# USB.net
KiCad netlist of a schematic drawn in Altium Designer
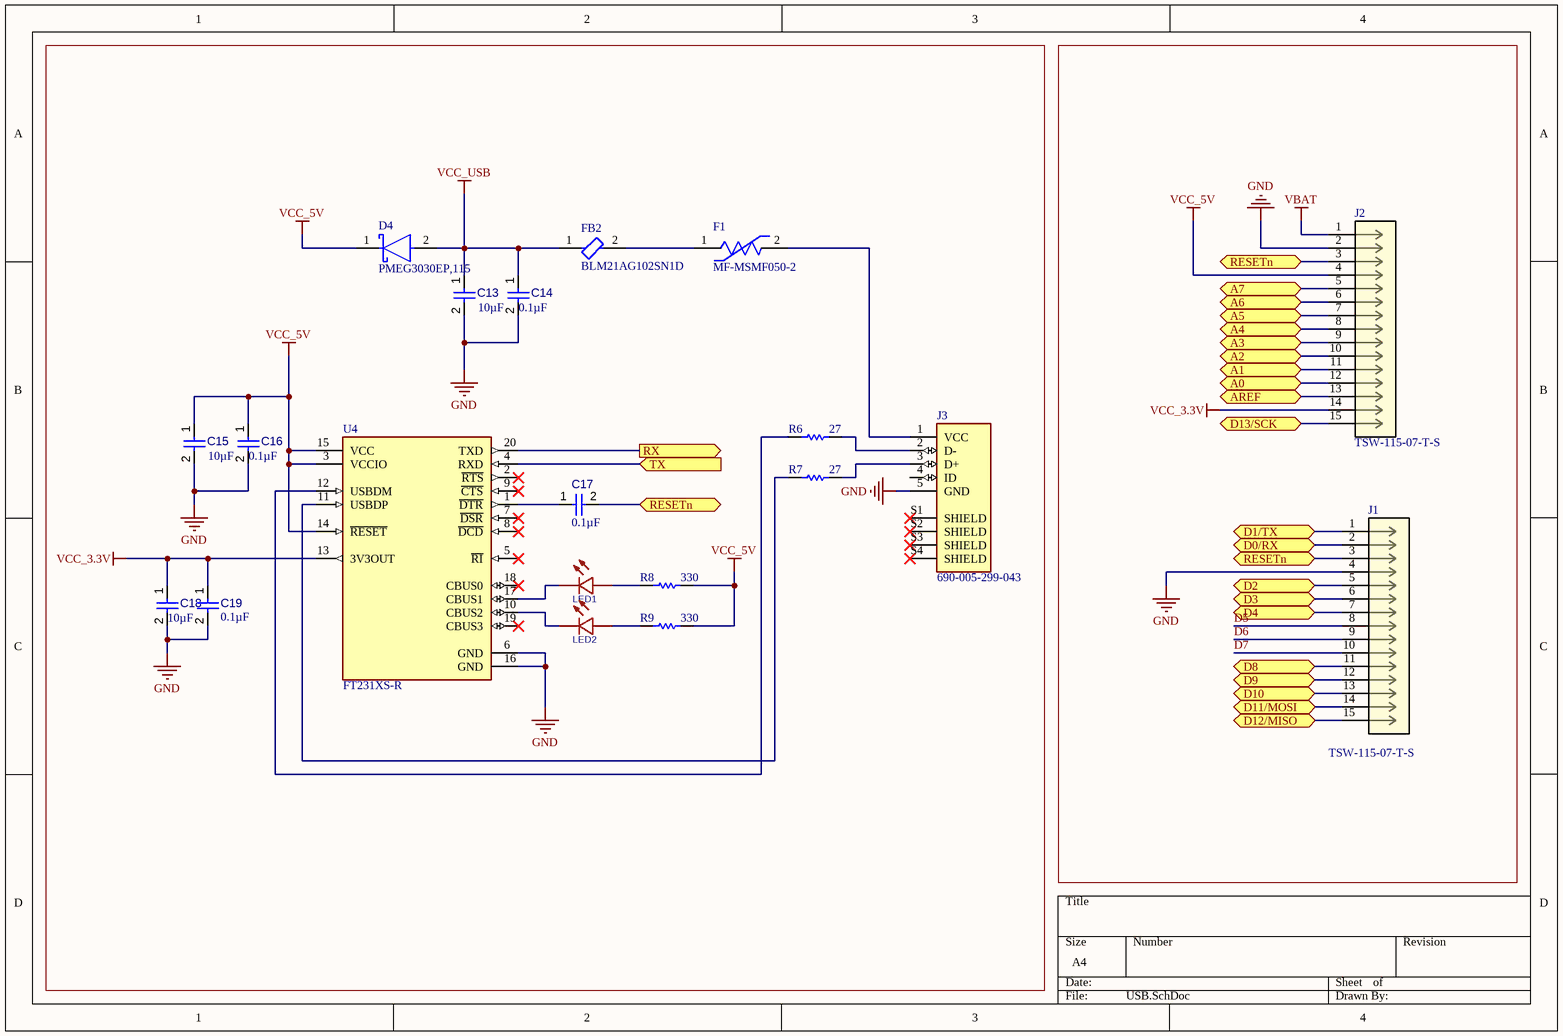
[diagram p0: USB.SchDoc]

(export (version "E")
  (design (tool "Eeschema 10.0.6"))
  (components
    (comp (ref "C13")
      (value "10µF")
      (footprint "CAPC2013X135X45NL10T25")
      (description "Chip Capacitor, 10 uF, +/- 10%, 16 V, 0805 (2012 Metric)")
      (fields (field (name "TOLERANCE") "10%") (field (name "Comment") "Capacitor 10 uF +/- 10% 16 V 0805"))
      (libsource (lib "新宇 付") (part "CAP-NP-2"))
    )
    (comp (ref "C14")
      (value "0.1µF")
      (footprint "CAPC2013X135X45NL10T25")
      (description "Chip Capacitor, 10 uF, +/- 10%, 16 V, 0805 (2012 Metric)")
      (fields (field (name "TOLERANCE") "10%") (field (name "Comment") "Capacitor 10 uF +/- 10% 16 V 0805"))
      (libsource (lib "新宇 付") (part "CAP-NP-2"))
    )
    (comp (ref "C15")
      (value "10µF")
      (footprint "CAPC2013X135X45NL10T25")
      (description "Chip Capacitor, 10 uF, +/- 10%, 16 V, 0805 (2012 Metric)")
      (fields (field (name "TOLERANCE") "10%") (field (name "Comment") "Capacitor 10 uF +/- 10% 16 V 0805"))
      (libsource (lib "新宇 付") (part "CAP-NP-2"))
    )
    (comp (ref "C16")
      (value "0.1µF")
      (footprint "CAPC2013X135X45NL10T25")
      (description "Chip Capacitor, 10 uF, +/- 10%, 16 V, 0805 (2012 Metric)")
      (fields (field (name "TOLERANCE") "10%") (field (name "Comment") "Capacitor 10 uF +/- 10% 16 V 0805"))
      (libsource (lib "新宇 付") (part "CAP-NP-2"))
    )
    (comp (ref "C17")
      (value "0.1µF")
      (footprint "CAPC2013X135X45NL10T25")
      (description "Chip Capacitor, 10 uF, +/- 10%, 16 V, 0805 (2012 Metric)")
      (fields (field (name "TOLERANCE") "10%") (field (name "Comment") "Capacitor 10 uF +/- 10% 16 V 0805"))
      (libsource (lib "新宇 付") (part "CAP-NP-2"))
    )
    (comp (ref "C18")
      (value "10µF")
      (footprint "CAPC2013X135X45NL10T25")
      (description "Chip Capacitor, 10 uF, +/- 10%, 16 V, 0805 (2012 Metric)")
      (fields (field (name "TOLERANCE") "10%") (field (name "Comment") "Capacitor 10 uF +/- 10% 16 V 0805"))
      (libsource (lib "新宇 付") (part "CAP-NP-2"))
    )
    (comp (ref "C19")
      (value "0.1µF")
      (footprint "CAPC2013X135X45NL10T25")
      (description "Chip Capacitor, 10 uF, +/- 10%, 16 V, 0805 (2012 Metric)")
      (fields (field (name "TOLERANCE") "10%") (field (name "Comment") "Capacitor 10 uF +/- 10% 16 V 0805"))
      (libsource (lib "新宇 付") (part "CAP-NP-2"))
    )
    (comp (ref "D4")
      (value "PMEG3030EP,115")
      (footprint "FP-SOD128-MFG")
      (description "DIODE SCHOTTKY 30V 3A SOD128")
      (libsource (lib "Altium Content Vault") (part "1d6ec82d83fb6aee721767c19dac4b9"))
    )
    (comp (ref "F1")
      (value "MF-MSMF050-2")
      (footprint "FP-MF-MSMF050-2-MFG")
      (description "PTC RESET FUSE 15V 500MA 1812")
      (fields
        (field (name "MANUFACTURER") "Bourns")
        (field (name "OCTOPART") "https://octopart.com/mf-msmf050-2-bourns-28047")
      )
      (libsource (lib "Altium Content Vault") (part "fc31388045fc42ab786d6d00b506e9f"))
    )
    (comp (ref "FB2")
      (value "BLM21AG102SN1D")
      (footprint "FP-BLM21-0_2-t0_85-e0_5-MFG")
      (description "Chip Ferrite Bead, 0805, 1000Ω @ 100MHz, 0.27Ω, 25%, 600mA")
      (fields (field (name "TOLERANCE") "25%"))
      (libsource (lib "Altium Content Vault") (part "5f30dd21d616792df468990f7003faa"))
    )
    (comp (ref "J1")
      (value "TSW-115-07-T-S")
      (footprint "CON15_1X15_TU_TSW")
      (description "No Description Available")
      (fields (field (name "COPYRIGHT") "Copyright (C) 2026 Ultra Librarian. All rights reserved."))
      (libsource (lib "TSW-115-07-T-S") (part "TSW-115-07-T-S"))
    )
    (comp (ref "J2")
      (value "TSW-115-07-T-S")
      (footprint "CON15_1X15_TU_TSW")
      (description "No Description Available")
      (fields (field (name "COPYRIGHT") "Copyright (C) 2026 Ultra Librarian. All rights reserved."))
      (libsource (lib "TSW-115-07-T-S") (part "TSW-115-07-T-S"))
    )
    (comp (ref "J3")
      (value "690-005-299-043")
      (footprint "690-005-299-043_EDA")
      (description "USB - mini B USB 2.0 Receptacle Connector 5 Position Surface Mount, Right Angle")
      (fields (field (name "MF") "EDAC Inc."))
      (libsource (lib "690-005-299-043") (part "690-005-299-043"))
    )
    (comp (ref "LED1")
      (value "FC-DA1608HRK-620D")
      (footprint "LED0603-RD_RED")
      (libsource (lib "C84263_发光二极管-LED_0603") (part "FC-DA1608HRK-620D"))
    )
    (comp (ref "LED2")
      (value "FC-DA1608HRK-620D")
      (footprint "LED0603-RD_RED")
      (libsource (lib "C84263_发光二极管-LED_0603") (part "FC-DA1608HRK-620D"))
    )
    (comp (ref "R6")
      (value "27")
      (footprint "RESC2013X50X35ML15T15")
      (description "Chip Resistor, 0 Ohm, +/- 1%, 125 mW, -55 to 155 degC, 0805 (2012 Metric)")
      (fields (field (name "TOLERANCE") "1%") (field (name "POWER") "125mW"))
      (libsource (lib "新宇 付") (part "RES-2"))
    )
    (comp (ref "R7")
      (value "27")
      (footprint "RESC2013X50X35ML15T15")
      (description "Chip Resistor, 0 Ohm, +/- 1%, 125 mW, -55 to 155 degC, 0805 (2012 Metric)")
      (fields (field (name "TOLERANCE") "1%") (field (name "POWER") "125mW"))
      (libsource (lib "新宇 付") (part "RES-2"))
    )
    (comp (ref "R8")
      (value "330")
      (footprint "RESC2013X50X35ML15T15")
      (description "Chip Resistor, 0 Ohm, +/- 1%, 125 mW, -55 to 155 degC, 0805 (2012 Metric)")
      (fields (field (name "TOLERANCE") "1%") (field (name "POWER") "125mW"))
      (libsource (lib "新宇 付") (part "RES-2"))
    )
    (comp (ref "R9")
      (value "330")
      (footprint "RESC2013X50X35ML15T15")
      (description "Chip Resistor, 0 Ohm, +/- 1%, 125 mW, -55 to 155 degC, 0805 (2012 Metric)")
      (fields (field (name "TOLERANCE") "1%") (field (name "POWER") "125mW"))
      (libsource (lib "新宇 付") (part "RES-2"))
    )
    (comp (ref "U4")
      (value "FT231XS-R")
      (footprint "FP-SSOP-20-MFG")
      (description "IC USB SERIAL FULL UART 20SSOP")
      (libsource (lib "Altium Content Vault") (part "6ea930917329caabf1041b50a9b81b2"))
    )
  )
  (nets
    (net (code "1") (name "/A0") (class "Default")
      (node (ref "J2") (pin "12") (pinfunction "12_12") (pintype "passive"))
    )
    (net (code "2") (name "/A1") (class "Default")
      (node (ref "J2") (pin "11") (pinfunction "11_11") (pintype "passive"))
    )
    (net (code "3") (name "/A2") (class "Default")
      (node (ref "J2") (pin "10") (pinfunction "10_10") (pintype "passive"))
    )
    (net (code "4") (name "/A3") (class "Default")
      (node (ref "J2") (pin "9") (pinfunction "9_9") (pintype "passive"))
    )
    (net (code "5") (name "/A4") (class "Default")
      (node (ref "J2") (pin "8") (pinfunction "8_8") (pintype "passive"))
    )
    (net (code "6") (name "/A5") (class "Default")
      (node (ref "J2") (pin "7") (pinfunction "7_7") (pintype "passive"))
    )
    (net (code "7") (name "/A6") (class "Default")
      (node (ref "J2") (pin "6") (pinfunction "6_6") (pintype "passive"))
    )
    (net (code "8") (name "/A7") (class "Default")
      (node (ref "J2") (pin "5") (pinfunction "5_5") (pintype "passive"))
    )
    (net (code "9") (name "/AREF") (class "Default")
      (node (ref "J2") (pin "13") (pinfunction "13_13") (pintype "passive"))
    )
    (net (code "10") (name "/D0{slash}RX") (class "Default")
      (node (ref "J1") (pin "2") (pinfunction "2_2") (pintype "passive"))
    )
    (net (code "11") (name "/D1{slash}TX") (class "Default")
      (node (ref "J1") (pin "1") (pinfunction "1_1") (pintype "passive"))
    )
    (net (code "12") (name "/D2") (class "Default")
      (node (ref "J1") (pin "5") (pinfunction "5_5") (pintype "passive"))
    )
    (net (code "13") (name "/D3") (class "Default")
      (node (ref "J1") (pin "6") (pinfunction "6_6") (pintype "passive"))
    )
    (net (code "14") (name "/D4") (class "Default")
      (node (ref "J1") (pin "7") (pinfunction "7_7") (pintype "passive"))
    )
    (net (code "15") (name "/D5") (class "Default")
      (node (ref "J1") (pin "8") (pinfunction "8_8") (pintype "passive"))
    )
    (net (code "16") (name "/D6") (class "Default")
      (node (ref "J1") (pin "9") (pinfunction "9_9") (pintype "passive"))
    )
    (net (code "17") (name "/D7") (class "Default")
      (node (ref "J1") (pin "10") (pinfunction "10_10") (pintype "passive"))
    )
    (net (code "18") (name "/D8") (class "Default")
      (node (ref "J1") (pin "11") (pinfunction "11_11") (pintype "passive"))
    )
    (net (code "19") (name "/D9") (class "Default")
      (node (ref "J1") (pin "12") (pinfunction "12_12") (pintype "passive"))
    )
    (net (code "20") (name "/D10") (class "Default")
      (node (ref "J1") (pin "13") (pinfunction "13_13") (pintype "passive"))
    )
    (net (code "21") (name "/D11{slash}MOSI") (class "Default")
      (node (ref "J1") (pin "14") (pinfunction "14_14") (pintype "passive"))
    )
    (net (code "22") (name "/D12{slash}MISO") (class "Default")
      (node (ref "J1") (pin "15") (pinfunction "15_15") (pintype "passive"))
    )
    (net (code "23") (name "/D13{slash}SCK") (class "Default")
      (node (ref "J2") (pin "15") (pinfunction "15_15") (pintype "passive"))
    )
    (net (code "24") (name "/RESETn") (class "Default")
      (node (ref "C17") (pin "2") (pinfunction "2_2") (pintype "passive"))
      (node (ref "J1") (pin "3") (pinfunction "3_3") (pintype "passive"))
      (node (ref "J2") (pin "3") (pinfunction "3_3") (pintype "passive"))
    )
    (net (code "25") (name "/RX") (class "Default")
      (node (ref "U4") (pin "20") (pinfunction "TXD_20") (pintype "output"))
    )
    (net (code "26") (name "/TX") (class "Default")
      (node (ref "U4") (pin "4") (pinfunction "RXD_4") (pintype "input"))
    )
    (net (code "27") (name "GND") (class "Default")
      (node (ref "C13") (pin "2") (pinfunction "2_2") (pintype "passive"))
      (node (ref "C14") (pin "2") (pinfunction "2_2") (pintype "passive"))
      (node (ref "C15") (pin "2") (pinfunction "2_2") (pintype "passive"))
      (node (ref "C16") (pin "2") (pinfunction "2_2") (pintype "passive"))
      (node (ref "C18") (pin "2") (pinfunction "2_2") (pintype "passive"))
      (node (ref "C19") (pin "2") (pinfunction "2_2") (pintype "passive"))
      (node (ref "J1") (pin "4") (pinfunction "4_4") (pintype "passive"))
      (node (ref "J2") (pin "2") (pinfunction "2_2") (pintype "passive"))
      (node (ref "J3") (pin "5") (pinfunction "GND_5") (pintype "power_in"))
      (node (ref "U4") (pin "16") (pinfunction "GND_16") (pintype "power_in"))
      (node (ref "U4") (pin "6") (pinfunction "GND_6") (pintype "power_in"))
    )
    (net (code "28") (name "Net-(F1-Pad1)") (class "Default")
      (node (ref "F1") (pin "1") (pinfunction "1_1") (pintype "passive"))
      (node (ref "FB2") (pin "2") (pinfunction "2_2") (pintype "passive"))
    )
    (net (code "29") (name "Net-(J3-D+)") (class "Default")
      (node (ref "J3") (pin "3") (pinfunction "D+_3") (pintype "bidirectional"))
      (node (ref "R7") (pin "2") (pinfunction "2_2") (pintype "passive"))
    )
    (net (code "30") (name "Net-(J3-D-)") (class "Default")
      (node (ref "J3") (pin "2") (pinfunction "D-_2") (pintype "bidirectional"))
      (node (ref "R6") (pin "2") (pinfunction "2_2") (pintype "passive"))
    )
    (net (code "31") (name "Net-(J3-VCC)") (class "Default")
      (node (ref "F1") (pin "2") (pinfunction "2_2") (pintype "passive"))
      (node (ref "J3") (pin "1") (pinfunction "VCC_1") (pintype "power_in"))
    )
    (net (code "32") (name "Net-(LED1-A)") (class "Default")
      (node (ref "LED1") (pin "2") (pinfunction "A_2") (pintype "passive"))
      (node (ref "R8") (pin "1") (pinfunction "1_1") (pintype "passive"))
    )
    (net (code "33") (name "Net-(LED1-K)") (class "Default")
      (node (ref "LED1") (pin "1") (pinfunction "K_1") (pintype "passive"))
      (node (ref "U4") (pin "17") (pinfunction "CBUS1_17") (pintype "bidirectional"))
    )
    (net (code "34") (name "Net-(LED2-A)") (class "Default")
      (node (ref "LED2") (pin "2") (pinfunction "A_2") (pintype "passive"))
      (node (ref "R9") (pin "1") (pinfunction "1_1") (pintype "passive"))
    )
    (net (code "35") (name "Net-(LED2-K)") (class "Default")
      (node (ref "LED2") (pin "1") (pinfunction "K_1") (pintype "passive"))
      (node (ref "U4") (pin "10") (pinfunction "CBUS2_10") (pintype "bidirectional"))
    )
    (net (code "36") (name "Net-(U4-USBDM)") (class "Default")
      (node (ref "R6") (pin "1") (pinfunction "1_1") (pintype "passive"))
      (node (ref "U4") (pin "12") (pinfunction "USBDM_12") (pintype "input"))
    )
    (net (code "37") (name "Net-(U4-USBDP)") (class "Default")
      (node (ref "R7") (pin "1") (pinfunction "1_1") (pintype "passive"))
      (node (ref "U4") (pin "11") (pinfunction "USBDP_11") (pintype "input"))
    )
    (net (code "38") (name "Net-(U4-~{DTR})") (class "Default")
      (node (ref "C17") (pin "1") (pinfunction "1_1") (pintype "passive"))
      (node (ref "U4") (pin "1") (pinfunction "~{DTR}_1") (pintype "output"))
    )
    (net (code "39") (name "VBAT") (class "Default")
      (node (ref "J2") (pin "1") (pinfunction "1_1") (pintype "passive"))
    )
    (net (code "40") (name "VCC_3.3V") (class "Default")
      (node (ref "C18") (pin "1") (pinfunction "1_1") (pintype "passive"))
      (node (ref "C19") (pin "1") (pinfunction "1_1") (pintype "passive"))
      (node (ref "J2") (pin "14") (pinfunction "14_14") (pintype "passive"))
      (node (ref "U4") (pin "13") (pinfunction "3V3OUT_13") (pintype "output"))
    )
    (net (code "41") (name "VCC_5V") (class "Default")
      (node (ref "C15") (pin "1") (pinfunction "1_1") (pintype "passive"))
      (node (ref "C16") (pin "1") (pinfunction "1_1") (pintype "passive"))
      (node (ref "D4") (pin "1") (pinfunction "C_1") (pintype "passive"))
      (node (ref "J2") (pin "4") (pinfunction "4_4") (pintype "passive"))
      (node (ref "R8") (pin "2") (pinfunction "2_2") (pintype "passive"))
      (node (ref "R9") (pin "2") (pinfunction "2_2") (pintype "passive"))
      (node (ref "U4") (pin "14") (pinfunction "~{RESET}_14") (pintype "input"))
      (node (ref "U4") (pin "15") (pinfunction "VCC_15") (pintype "power_in"))
      (node (ref "U4") (pin "3") (pinfunction "VCCIO_3") (pintype "power_in"))
    )
    (net (code "42") (name "VCC_USB") (class "Default")
      (node (ref "C13") (pin "1") (pinfunction "1_1") (pintype "passive"))
      (node (ref "C14") (pin "1") (pinfunction "1_1") (pintype "passive"))
      (node (ref "D4") (pin "2") (pinfunction "A_2") (pintype "passive"))
      (node (ref "FB2") (pin "1") (pinfunction "1_1") (pintype "passive"))
    )
    (net (code "43") (name "unconnected-(J3-ID-Pad4)") (class "Default")
      (node (ref "J3") (pin "4") (pinfunction "ID_4") (pintype "bidirectional"))
    )
    (net (code "44") (name "unconnected-(J3-SHIELD-PadS1)") (class "Default")
      (node (ref "J3") (pin "S1") (pinfunction "SHIELD_S1") (pintype "passive+no_connect"))
    )
    (net (code "45") (name "unconnected-(J3-SHIELD-PadS2)") (class "Default")
      (node (ref "J3") (pin "S2") (pinfunction "SHIELD_S2") (pintype "passive+no_connect"))
    )
    (net (code "46") (name "unconnected-(J3-SHIELD-PadS3)") (class "Default")
      (node (ref "J3") (pin "S3") (pinfunction "SHIELD_S3") (pintype "passive+no_connect"))
    )
    (net (code "47") (name "unconnected-(J3-SHIELD-PadS4)") (class "Default")
      (node (ref "J3") (pin "S4") (pinfunction "SHIELD_S4") (pintype "passive+no_connect"))
    )
    (net (code "48") (name "unconnected-(U4-CBUS0-Pad18)") (class "Default")
      (node (ref "U4") (pin "18") (pinfunction "CBUS0_18") (pintype "bidirectional+no_connect"))
    )
    (net (code "49") (name "unconnected-(U4-CBUS3-Pad19)") (class "Default")
      (node (ref "U4") (pin "19") (pinfunction "CBUS3_19") (pintype "bidirectional+no_connect"))
    )
    (net (code "50") (name "unconnected-(U4-~{CTS}-Pad9)") (class "Default")
      (node (ref "U4") (pin "9") (pinfunction "~{CTS}_9") (pintype "input+no_connect"))
    )
    (net (code "51") (name "unconnected-(U4-~{DCD}-Pad8)") (class "Default")
      (node (ref "U4") (pin "8") (pinfunction "~{DCD}_8") (pintype "input+no_connect"))
    )
    (net (code "52") (name "unconnected-(U4-~{DSR}-Pad7)") (class "Default")
      (node (ref "U4") (pin "7") (pinfunction "~{DSR}_7") (pintype "input+no_connect"))
    )
    (net (code "53") (name "unconnected-(U4-~{RI}-Pad5)") (class "Default")
      (node (ref "U4") (pin "5") (pinfunction "~{RI}_5") (pintype "input+no_connect"))
    )
    (net (code "54") (name "unconnected-(U4-~{RTS}-Pad2)") (class "Default")
      (node (ref "U4") (pin "2") (pinfunction "~{RTS}_2") (pintype "output+no_connect"))
    )
  )
)
